# dome-board4.net
KiCad netlist of a schematic drawn in EAGLE
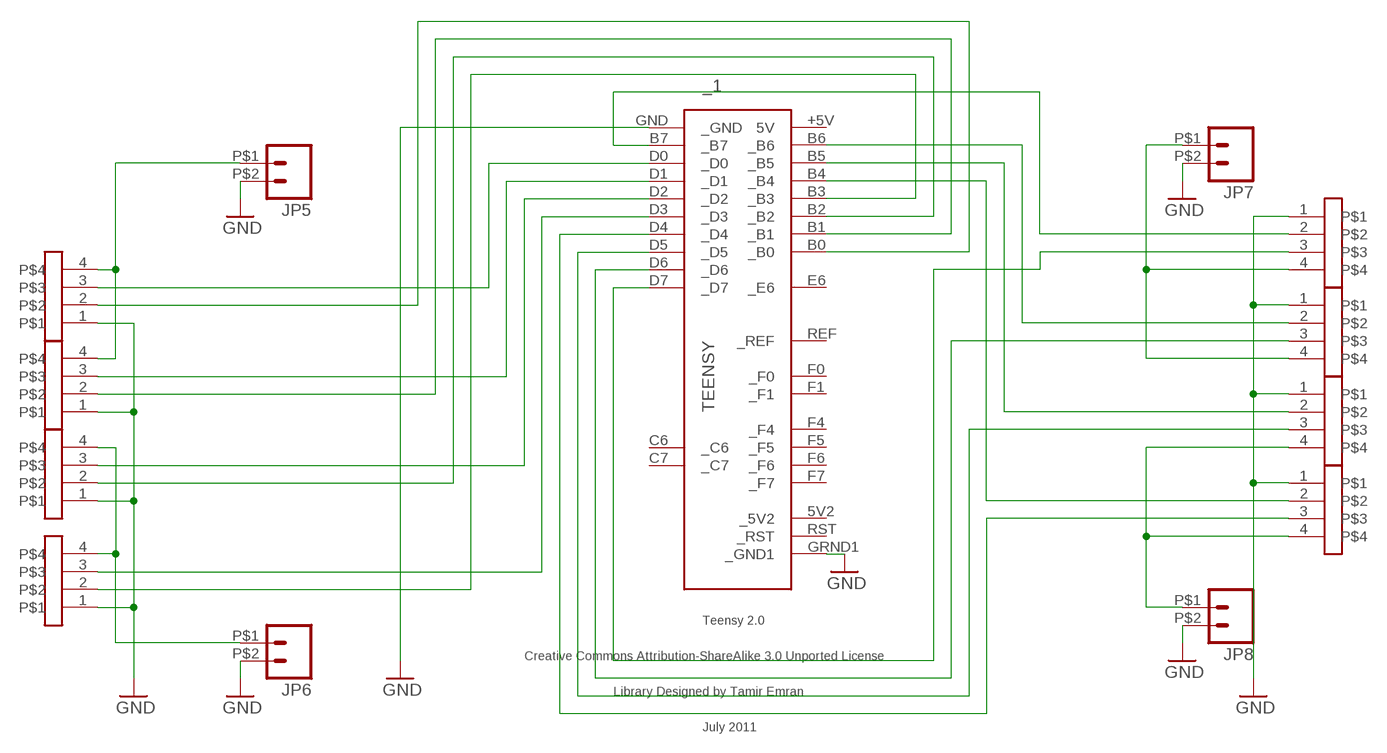
[diagram p0: schematic, sheet 1]

(export (version "E")
  (design (tool "Eeschema 10.0.6"))
  (components
    (comp (ref "JP5")
      (value "M026.35MM")
      (footprint "eagle-import:SCREWTERMINAL-6.35MM-2")
      (libsource (lib "eagle-import") (part "M026.35MM"))
    )
    (comp (ref "JP6")
      (value "M026.35MM")
      (footprint "eagle-import:SCREWTERMINAL-6.35MM-2")
      (libsource (lib "eagle-import") (part "M026.35MM"))
    )
    (comp (ref "JP7")
      (value "M026.35MM")
      (footprint "eagle-import:SCREWTERMINAL-6.35MM-2")
      (libsource (lib "eagle-import") (part "M026.35MM"))
    )
    (comp (ref "JP8")
      (value "M026.35MM")
      (footprint "eagle-import:SCREWTERMINAL-6.35MM-2")
      (libsource (lib "eagle-import") (part "M026.35MM"))
    )
    (comp (ref "U$1")
      (value "M04")
      (footprint "eagle-import:1X04-2EDG-350")
      (libsource (lib "eagle-import") (part "M04"))
    )
    (comp (ref "U$2")
      (value "M04")
      (footprint "eagle-import:1X04-2EDG-350")
      (libsource (lib "eagle-import") (part "M04"))
    )
    (comp (ref "U$3")
      (value "M04")
      (footprint "eagle-import:1X04-2EDG-350")
      (libsource (lib "eagle-import") (part "M04"))
    )
    (comp (ref "U$4")
      (value "M04")
      (footprint "eagle-import:1X04-2EDG-350")
      (libsource (lib "eagle-import") (part "M04"))
    )
    (comp (ref "U$5")
      (value "M04")
      (footprint "eagle-import:1X04-2EDG-350")
      (libsource (lib "eagle-import") (part "M04"))
    )
    (comp (ref "U$6")
      (value "M04")
      (footprint "eagle-import:1X04-2EDG-350")
      (libsource (lib "eagle-import") (part "M04"))
    )
    (comp (ref "U$7")
      (value "M04")
      (footprint "eagle-import:1X04-2EDG-350")
      (libsource (lib "eagle-import") (part "M04"))
    )
    (comp (ref "U$8")
      (value "M04")
      (footprint "eagle-import:1X04-2EDG-350")
      (libsource (lib "eagle-import") (part "M04"))
    )
    (comp (ref "_1")
      (value "TEENSY")
      (footprint "eagle-import:TEENSY")
      (libsource (lib "eagle-import") (part "TEENSY"))
    )
  )
  (nets
    (net (code "1") (name "GND") (class "Default")
      (node (ref "JP5") (pin "P$2") (pinfunction "2_P$2") (pintype "passive"))
      (node (ref "JP6") (pin "P$2") (pinfunction "2_P$2") (pintype "passive"))
      (node (ref "JP7") (pin "P$2") (pinfunction "2_P$2") (pintype "passive"))
      (node (ref "JP8") (pin "P$2") (pinfunction "2_P$2") (pintype "passive"))
      (node (ref "U$1") (pin "1") (pinfunction "P$1_1") (pintype "bidirectional"))
      (node (ref "U$2") (pin "1") (pinfunction "P$1_1") (pintype "bidirectional"))
      (node (ref "U$3") (pin "1") (pinfunction "P$1_1") (pintype "bidirectional"))
      (node (ref "U$4") (pin "1") (pinfunction "P$1_1") (pintype "bidirectional"))
      (node (ref "U$5") (pin "1") (pinfunction "P$1_1") (pintype "bidirectional"))
      (node (ref "U$6") (pin "1") (pinfunction "P$1_1") (pintype "bidirectional"))
      (node (ref "U$7") (pin "1") (pinfunction "P$1_1") (pintype "bidirectional"))
      (node (ref "U$8") (pin "1") (pinfunction "P$1_1") (pintype "bidirectional"))
      (node (ref "_1") (pin "GND") (pinfunction "_GND_GND") (pintype "bidirectional"))
      (node (ref "_1") (pin "GRND1") (pinfunction "_GND1_GRND1") (pintype "bidirectional"))
    )
    (net (code "2") (name "Net-(JP5-1)") (class "Default")
      (node (ref "JP5") (pin "P$1") (pinfunction "1_P$1") (pintype "passive"))
      (node (ref "U$1") (pin "4") (pinfunction "P$4_4") (pintype "bidirectional"))
      (node (ref "U$2") (pin "4") (pinfunction "P$4_4") (pintype "bidirectional"))
    )
    (net (code "3") (name "Net-(JP6-1)") (class "Default")
      (node (ref "JP6") (pin "P$1") (pinfunction "1_P$1") (pintype "passive"))
      (node (ref "U$3") (pin "4") (pinfunction "P$4_4") (pintype "bidirectional"))
      (node (ref "U$4") (pin "4") (pinfunction "P$4_4") (pintype "bidirectional"))
    )
    (net (code "4") (name "Net-(JP7-1)") (class "Default")
      (node (ref "JP7") (pin "P$1") (pinfunction "1_P$1") (pintype "passive"))
      (node (ref "U$5") (pin "4") (pinfunction "P$4_4") (pintype "bidirectional"))
      (node (ref "U$6") (pin "4") (pinfunction "P$4_4") (pintype "bidirectional"))
    )
    (net (code "5") (name "Net-(JP8-1)") (class "Default")
      (node (ref "JP8") (pin "P$1") (pinfunction "1_P$1") (pintype "passive"))
      (node (ref "U$7") (pin "4") (pinfunction "P$4_4") (pintype "bidirectional"))
      (node (ref "U$8") (pin "4") (pinfunction "P$4_4") (pintype "bidirectional"))
    )
    (net (code "6") (name "Net-(U$1-P$2)") (class "Default")
      (node (ref "U$1") (pin "2") (pinfunction "P$2_2") (pintype "bidirectional"))
      (node (ref "_1") (pin "B0") (pinfunction "_B0_B0") (pintype "bidirectional"))
    )
    (net (code "7") (name "Net-(U$1-P$3)") (class "Default")
      (node (ref "U$1") (pin "3") (pinfunction "P$3_3") (pintype "bidirectional"))
      (node (ref "_1") (pin "D0") (pinfunction "_D0_D0") (pintype "bidirectional"))
    )
    (net (code "8") (name "Net-(U$2-P$2)") (class "Default")
      (node (ref "U$2") (pin "2") (pinfunction "P$2_2") (pintype "bidirectional"))
      (node (ref "_1") (pin "B1") (pinfunction "_B1_B1") (pintype "bidirectional"))
    )
    (net (code "9") (name "Net-(U$2-P$3)") (class "Default")
      (node (ref "U$2") (pin "3") (pinfunction "P$3_3") (pintype "bidirectional"))
      (node (ref "_1") (pin "D1") (pinfunction "_D1_D1") (pintype "bidirectional"))
    )
    (net (code "10") (name "Net-(U$3-P$2)") (class "Default")
      (node (ref "U$3") (pin "2") (pinfunction "P$2_2") (pintype "bidirectional"))
      (node (ref "_1") (pin "B2") (pinfunction "_B2_B2") (pintype "bidirectional"))
    )
    (net (code "11") (name "Net-(U$3-P$3)") (class "Default")
      (node (ref "U$3") (pin "3") (pinfunction "P$3_3") (pintype "bidirectional"))
      (node (ref "_1") (pin "D2") (pinfunction "_D2_D2") (pintype "bidirectional"))
    )
    (net (code "12") (name "Net-(U$4-P$2)") (class "Default")
      (node (ref "U$4") (pin "2") (pinfunction "P$2_2") (pintype "bidirectional"))
      (node (ref "_1") (pin "B3") (pinfunction "_B3_B3") (pintype "bidirectional"))
    )
    (net (code "13") (name "Net-(U$4-P$3)") (class "Default")
      (node (ref "U$4") (pin "3") (pinfunction "P$3_3") (pintype "bidirectional"))
      (node (ref "_1") (pin "D3") (pinfunction "_D3_D3") (pintype "bidirectional"))
    )
    (net (code "14") (name "Net-(U$5-P$2)") (class "Default")
      (node (ref "U$5") (pin "2") (pinfunction "P$2_2") (pintype "bidirectional"))
      (node (ref "_1") (pin "B7") (pinfunction "_B7_B7") (pintype "bidirectional"))
    )
    (net (code "15") (name "Net-(U$5-P$3)") (class "Default")
      (node (ref "U$5") (pin "3") (pinfunction "P$3_3") (pintype "bidirectional"))
      (node (ref "_1") (pin "D7") (pinfunction "_D7_D7") (pintype "bidirectional"))
    )
    (net (code "16") (name "Net-(U$6-P$2)") (class "Default")
      (node (ref "U$6") (pin "2") (pinfunction "P$2_2") (pintype "bidirectional"))
      (node (ref "_1") (pin "B6") (pinfunction "_B6_B6") (pintype "bidirectional"))
    )
    (net (code "17") (name "Net-(U$6-P$3)") (class "Default")
      (node (ref "U$6") (pin "3") (pinfunction "P$3_3") (pintype "bidirectional"))
      (node (ref "_1") (pin "D6") (pinfunction "_D6_D6") (pintype "bidirectional"))
    )
    (net (code "18") (name "Net-(U$7-P$2)") (class "Default")
      (node (ref "U$7") (pin "2") (pinfunction "P$2_2") (pintype "bidirectional"))
      (node (ref "_1") (pin "B5") (pinfunction "_B5_B5") (pintype "bidirectional"))
    )
    (net (code "19") (name "Net-(U$7-P$3)") (class "Default")
      (node (ref "U$7") (pin "3") (pinfunction "P$3_3") (pintype "bidirectional"))
      (node (ref "_1") (pin "D5") (pinfunction "_D5_D5") (pintype "bidirectional"))
    )
    (net (code "20") (name "Net-(U$8-P$2)") (class "Default")
      (node (ref "U$8") (pin "2") (pinfunction "P$2_2") (pintype "bidirectional"))
      (node (ref "_1") (pin "B4") (pinfunction "_B4_B4") (pintype "bidirectional"))
    )
    (net (code "21") (name "Net-(U$8-P$3)") (class "Default")
      (node (ref "U$8") (pin "3") (pinfunction "P$3_3") (pintype "bidirectional"))
      (node (ref "_1") (pin "D4") (pinfunction "_D4_D4") (pintype "bidirectional"))
    )
    (net (code "22") (name "unconnected-(_1-5V-Pad+5V)") (class "Default")
      (node (ref "_1") (pin "+5V") (pinfunction "5V_+5V") (pintype "bidirectional"))
    )
    (net (code "23") (name "unconnected-(_1-_5V2-Pad5V2)") (class "Default")
      (node (ref "_1") (pin "5V2") (pinfunction "_5V2_5V2") (pintype "bidirectional"))
    )
    (net (code "24") (name "unconnected-(_1-_C6-PadC6)") (class "Default")
      (node (ref "_1") (pin "C6") (pinfunction "_C6_C6") (pintype "bidirectional"))
    )
    (net (code "25") (name "unconnected-(_1-_C7-PadC7)") (class "Default")
      (node (ref "_1") (pin "C7") (pinfunction "_C7_C7") (pintype "bidirectional"))
    )
    (net (code "26") (name "unconnected-(_1-_E6-PadE6)") (class "Default")
      (node (ref "_1") (pin "E6") (pinfunction "_E6_E6") (pintype "bidirectional"))
    )
    (net (code "27") (name "unconnected-(_1-_F0-PadF0)") (class "Default")
      (node (ref "_1") (pin "F0") (pinfunction "_F0_F0") (pintype "bidirectional"))
    )
    (net (code "28") (name "unconnected-(_1-_F1-PadF1)") (class "Default")
      (node (ref "_1") (pin "F1") (pinfunction "_F1_F1") (pintype "bidirectional"))
    )
    (net (code "29") (name "unconnected-(_1-_F4-PadF4)") (class "Default")
      (node (ref "_1") (pin "F4") (pinfunction "_F4_F4") (pintype "bidirectional"))
    )
    (net (code "30") (name "unconnected-(_1-_F5-PadF5)") (class "Default")
      (node (ref "_1") (pin "F5") (pinfunction "_F5_F5") (pintype "bidirectional"))
    )
    (net (code "31") (name "unconnected-(_1-_F6-PadF6)") (class "Default")
      (node (ref "_1") (pin "F6") (pinfunction "_F6_F6") (pintype "bidirectional"))
    )
    (net (code "32") (name "unconnected-(_1-_F7-PadF7)") (class "Default")
      (node (ref "_1") (pin "F7") (pinfunction "_F7_F7") (pintype "bidirectional"))
    )
    (net (code "33") (name "unconnected-(_1-_REF-PadREF)") (class "Default")
      (node (ref "_1") (pin "REF") (pinfunction "_REF_REF") (pintype "bidirectional"))
    )
    (net (code "34") (name "unconnected-(_1-_RST-PadRST)") (class "Default")
      (node (ref "_1") (pin "RST") (pinfunction "_RST_RST") (pintype "bidirectional"))
    )
  )
)
